# SCH_power_2025-01-19.net
KiCad netlist of a schematic drawn in EasyEDA
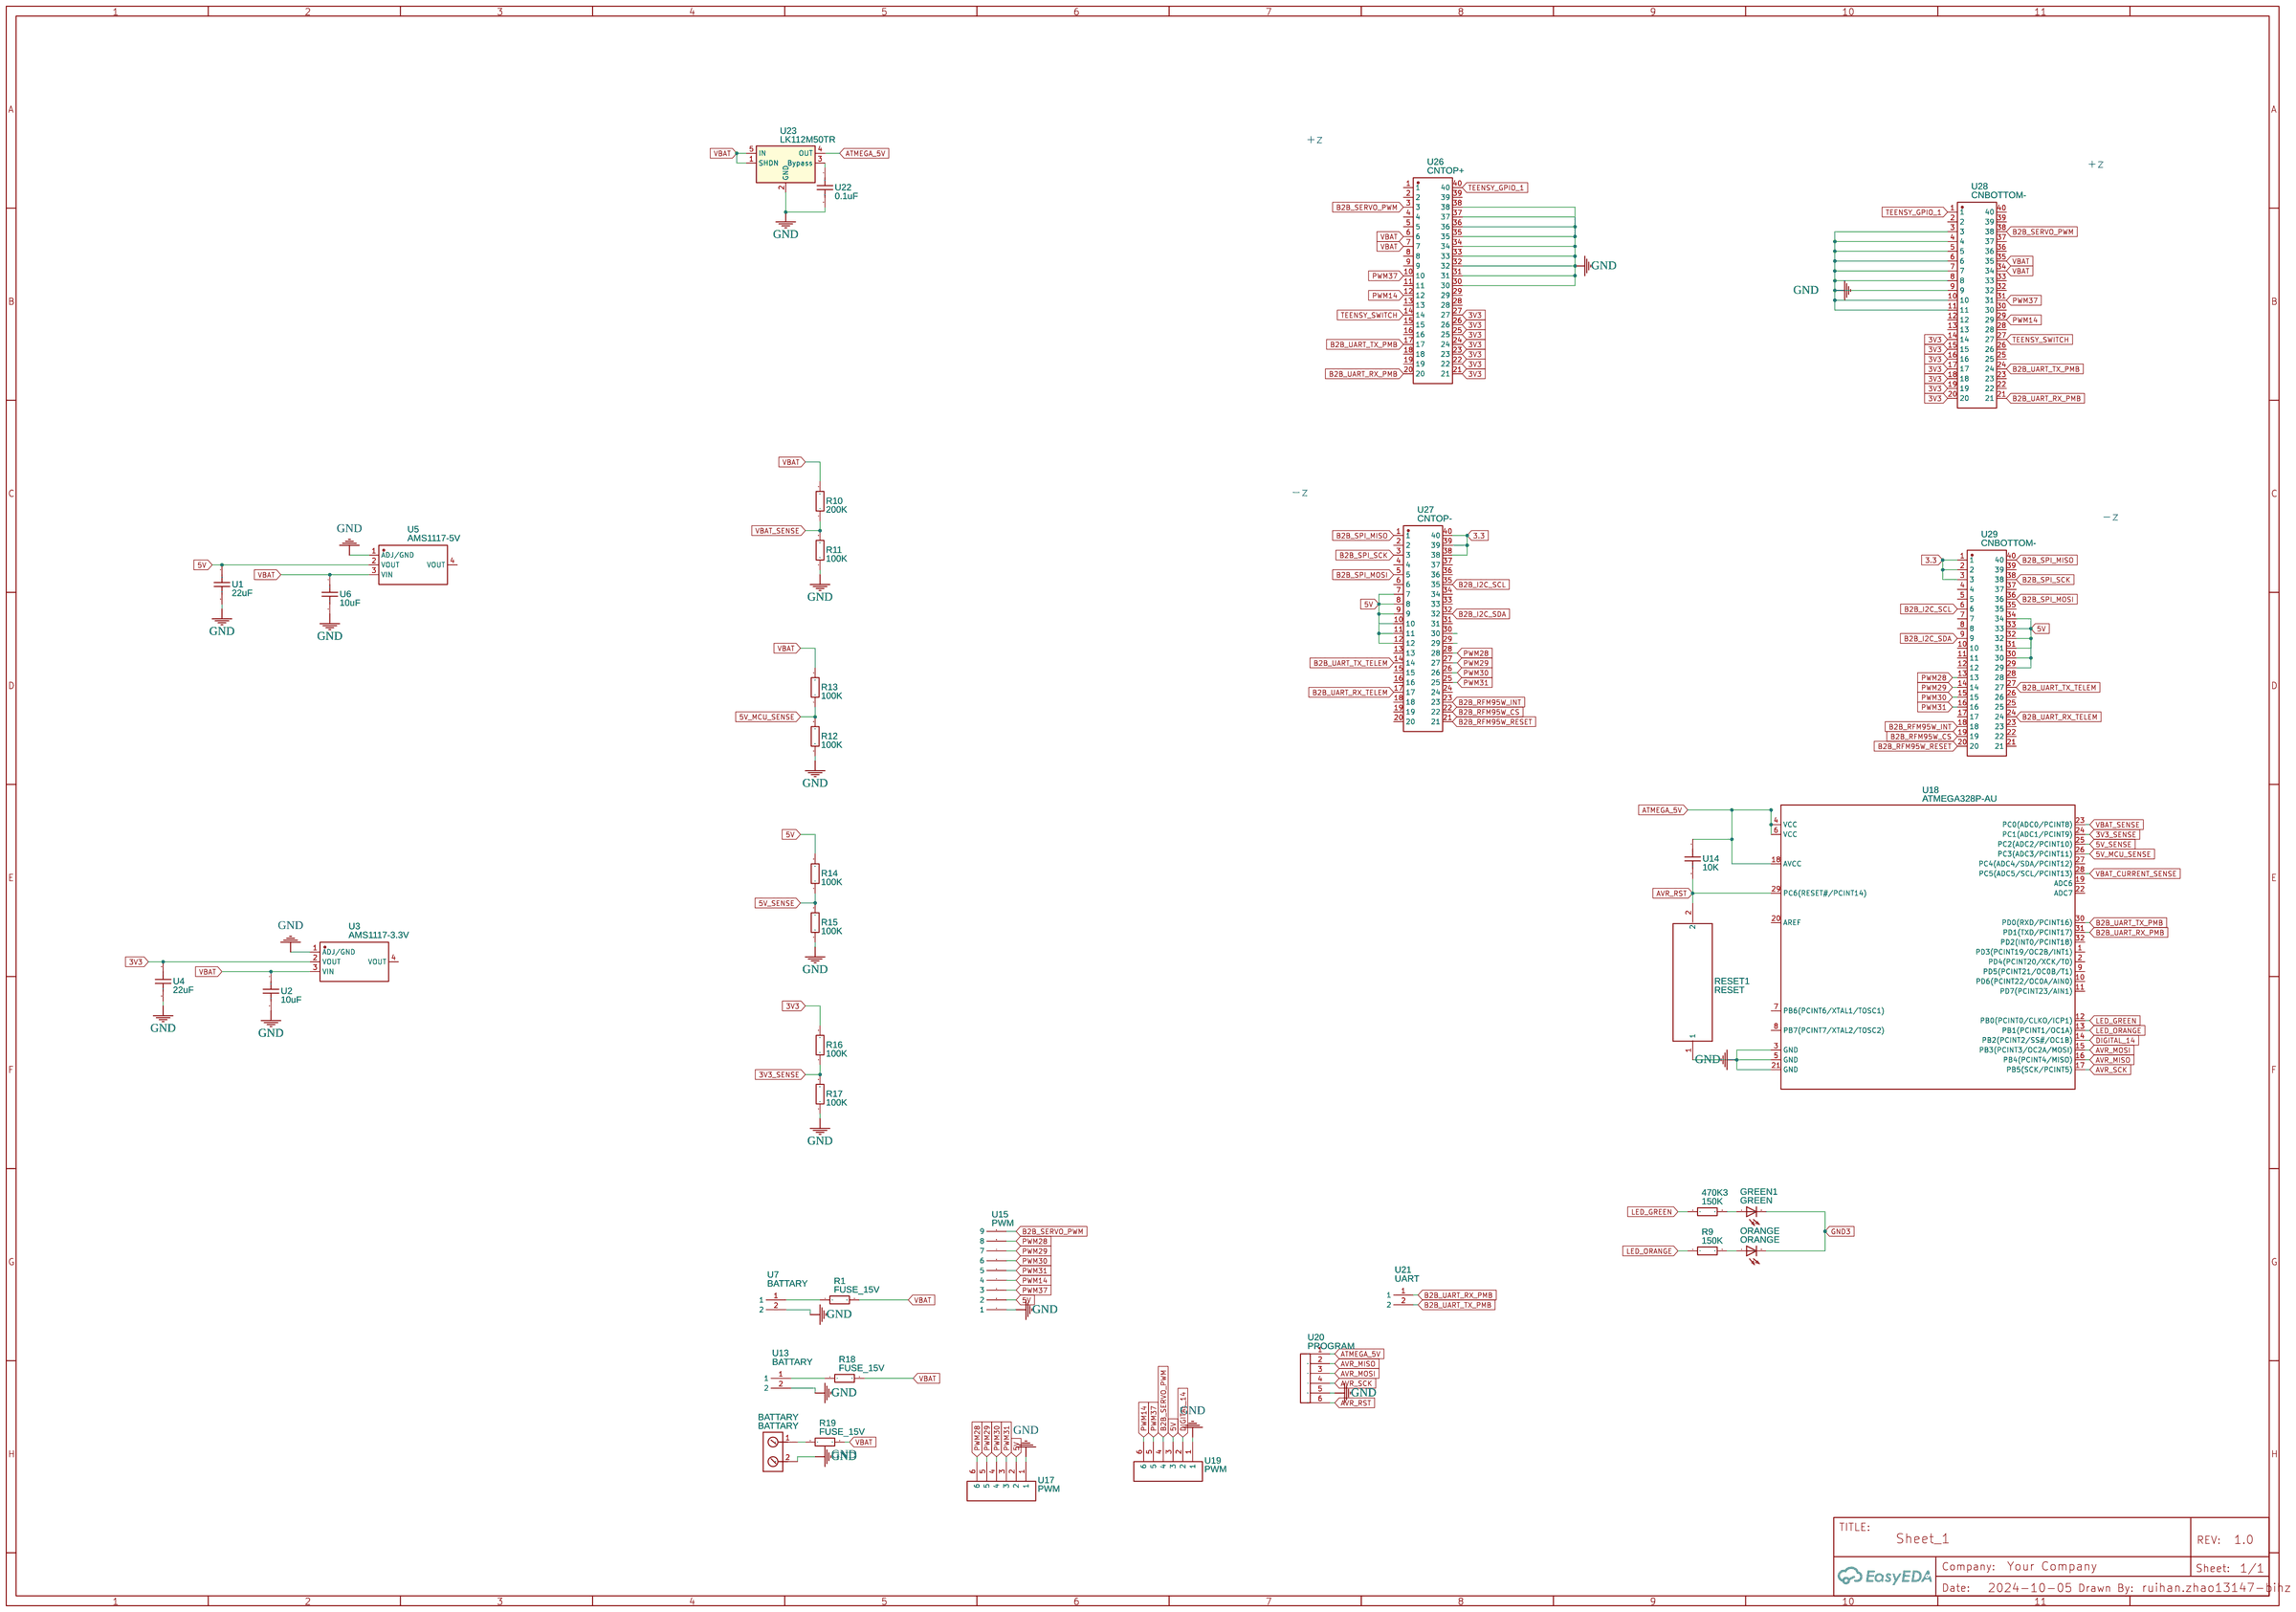
[diagram p0: schematic sheet]

(export (version "E")
  (design (tool "Eeschema 10.0.6"))
  (components
    (comp (ref "470K3") (value "150K") (libsource (lib "") (part "0805 Resistor")))
    (comp (ref "BATTARY") (value "BATTARY") (libsource (lib "") (part "STB-5MM-2PIN")))
    (comp (ref "GREEN1") (value "GREEN") (libsource (lib "") (part "LEDCHIP-LED0805_1")))
    (comp (ref "ORANGE") (value "ORANGE") (libsource (lib "") (part "LEDCHIP-LED0805")))
    (comp (ref "R1")
      (value "FUSE_15V")
      (fields (field (name "Manufacturer Part") "0805"))
      (libsource (lib "") (part "0805_1"))
    )
    (comp (ref "R9") (value "150K") (libsource (lib "") (part "0805 Resistor_1")))
    (comp (ref "R10")
      (value "200K")
      (fields (field (name "Manufacturer Part") "0805"))
      (libsource (lib "") (part "0805"))
    )
    (comp (ref "R11")
      (value "100K")
      (fields (field (name "Manufacturer Part") "0805"))
      (libsource (lib "") (part "0805"))
    )
    (comp (ref "R12")
      (value "100K")
      (fields (field (name "Manufacturer Part") "0805"))
      (libsource (lib "") (part "0805"))
    )
    (comp (ref "R13")
      (value "100K")
      (fields (field (name "Manufacturer Part") "0805"))
      (libsource (lib "") (part "0805"))
    )
    (comp (ref "R14")
      (value "100K")
      (fields (field (name "Manufacturer Part") "0805"))
      (libsource (lib "") (part "0805"))
    )
    (comp (ref "R15")
      (value "100K")
      (fields (field (name "Manufacturer Part") "0805"))
      (libsource (lib "") (part "0805"))
    )
    (comp (ref "R16")
      (value "100K")
      (fields (field (name "Manufacturer Part") "0805"))
      (libsource (lib "") (part "0805"))
    )
    (comp (ref "R17")
      (value "100K")
      (fields (field (name "Manufacturer Part") "0805"))
      (libsource (lib "") (part "0805"))
    )
    (comp (ref "R18")
      (value "FUSE_15V")
      (fields (field (name "Manufacturer Part") "0805"))
      (libsource (lib "") (part "0805_1"))
    )
    (comp (ref "R19")
      (value "FUSE_15V")
      (fields (field (name "Manufacturer Part") "0805"))
      (libsource (lib "") (part "0805_1"))
    )
    (comp (ref "RESET1") (value "RESET") (libsource (lib "") (part "FSMSM")))
    (comp (ref "U1")
      (value "22uF")
      (fields (field (name "Manufacturer Part") "CAP-C0805"))
      (libsource (lib "") (part "CAP-C0805"))
    )
    (comp (ref "U2")
      (value "10uF")
      (fields (field (name "Manufacturer Part") "CAP-C0805"))
      (libsource (lib "") (part "CAP-C0805"))
    )
    (comp (ref "U3")
      (value "AMS1117-3.3V")
      (fields (field (name "Manufacturer") "WPMtek(维攀)"))
      (libsource (lib "") (part "AMS1117-3.3V"))
    )
    (comp (ref "U4")
      (value "22uF")
      (fields (field (name "Manufacturer Part") "CAP-C0805"))
      (libsource (lib "") (part "CAP-C0805"))
    )
    (comp (ref "U5")
      (value "AMS1117-5V")
      (fields (field (name "Manufacturer Part") "AMS1117-3.3V") (field (name "Manufacturer") "WPMtek(维攀)"))
      (libsource (lib "") (part "AMS1117-3.3V"))
    )
    (comp (ref "U6")
      (value "10uF")
      (fields (field (name "Manufacturer Part") "CAP-C0805"))
      (libsource (lib "") (part "CAP-C0805"))
    )
    (comp (ref "U7") (value "BATTARY") (libsource (lib "") (part "2 pin header")))
    (comp (ref "U13") (value "BATTARY") (libsource (lib "") (part "2 pin header")))
    (comp (ref "U14")
      (value "10K")
      (fields (field (name "Manufacturer Part") "CAP-C0805"))
      (libsource (lib "") (part "CAP-C0805"))
    )
    (comp (ref "U15")
      (value "PWM")
      (fields (field (name "Manufacturer Part") "6 Pin Header"))
      (libsource (lib "") (part "9 Pin Header"))
    )
    (comp (ref "U17") (value "PWM") (libsource (lib "") (part "6PIN_5MM")))
    (comp (ref "U18") (value "ATMEGA328P-AU") (libsource (lib "") (part "ATMEGA328P-AU")))
    (comp (ref "U19") (value "PWM") (libsource (lib "") (part "6PIN_5MM")))
    (comp (ref "U20") (value "PROGRAM") (libsource (lib "") (part "6 pin header")))
    (comp (ref "U21") (value "UART") (libsource (lib "") (part "2 pin header")))
    (comp (ref "U22")
      (value "0.1uF")
      (fields (field (name "Manufacturer Part") "CAP-C0805"))
      (libsource (lib "") (part "CAP-C0805"))
    )
    (comp (ref "U23") (value "LK112M50TR") (libsource (lib "") (part "LK112M50TR")))
    (comp (ref "U26")
      (value "CNTOP+")
      (fields (field (name "Manufacturer Part") "SGDBM-08-40P"))
      (libsource (lib "") (part "SGDBM-08-40P"))
    )
    (comp (ref "U27")
      (value "CNTOP-")
      (fields (field (name "Manufacturer Part") "SGDBM-08-40P"))
      (libsource (lib "") (part "SGDBM-08-40P"))
    )
    (comp (ref "U28")
      (value "CNBOTTOM-")
      (fields (field (name "Manufacturer Part") "SGDBM-08-40P"))
      (libsource (lib "") (part "SGDBM-08-40P"))
    )
    (comp (ref "U29")
      (value "CNBOTTOM-")
      (fields (field (name "Manufacturer Part") "SGDBM-08-40P"))
      (libsource (lib "") (part "SGDBM-08-40P"))
    )
  )
  (nets
    (net (code "1") (name "3.3") (class "Default")
      (node (ref "U27") (pin "38") (pinfunction "38_38") (pintype "unspecified"))
      (node (ref "U27") (pin "39") (pinfunction "39_39") (pintype "unspecified"))
      (node (ref "U27") (pin "40") (pinfunction "40_40") (pintype "unspecified"))
      (node (ref "U29") (pin "1") (pinfunction "1_1") (pintype "unspecified"))
      (node (ref "U29") (pin "2") (pinfunction "2_2") (pintype "unspecified"))
      (node (ref "U29") (pin "3") (pinfunction "3_3") (pintype "unspecified"))
    )
    (net (code "2") (name "3V3") (class "Default")
      (node (ref "R16") (pin "2") (pinfunction "2_2") (pintype "unspecified"))
      (node (ref "U26") (pin "21") (pinfunction "21_21") (pintype "unspecified"))
      (node (ref "U26") (pin "22") (pinfunction "22_22") (pintype "unspecified"))
      (node (ref "U26") (pin "23") (pinfunction "23_23") (pintype "unspecified"))
      (node (ref "U26") (pin "24") (pinfunction "24_24") (pintype "unspecified"))
      (node (ref "U26") (pin "25") (pinfunction "25_25") (pintype "unspecified"))
      (node (ref "U26") (pin "26") (pinfunction "26_26") (pintype "unspecified"))
      (node (ref "U26") (pin "27") (pinfunction "27_27") (pintype "unspecified"))
      (node (ref "U28") (pin "14") (pinfunction "14_14") (pintype "unspecified"))
      (node (ref "U28") (pin "15") (pinfunction "15_15") (pintype "unspecified"))
      (node (ref "U28") (pin "16") (pinfunction "16_16") (pintype "unspecified"))
      (node (ref "U28") (pin "17") (pinfunction "17_17") (pintype "unspecified"))
      (node (ref "U28") (pin "18") (pinfunction "18_18") (pintype "unspecified"))
      (node (ref "U28") (pin "19") (pinfunction "19_19") (pintype "unspecified"))
      (node (ref "U28") (pin "20") (pinfunction "20_20") (pintype "unspecified"))
      (node (ref "U3") (pin "2") (pinfunction "VOUT_2") (pintype "unspecified"))
      (node (ref "U4") (pin "1") (pinfunction "1_1") (pintype "unspecified"))
    )
    (net (code "3") (name "3V3_SENSE") (class "Default")
      (node (ref "R16") (pin "1") (pinfunction "1_1") (pintype "unspecified"))
      (node (ref "R17") (pin "2") (pinfunction "2_2") (pintype "unspecified"))
      (node (ref "U18") (pin "24") (pinfunction "PC1(ADC1/PCINT9)_24") (pintype "unspecified"))
    )
    (net (code "4") (name "5V") (class "Default")
      (node (ref "R14") (pin "2") (pinfunction "2_2") (pintype "unspecified"))
      (node (ref "U1") (pin "1") (pinfunction "1_1") (pintype "unspecified"))
      (node (ref "U15") (pin "2") (pinfunction "2_2") (pintype "unspecified"))
      (node (ref "U17") (pin "2") (pinfunction "2_2") (pintype "unspecified"))
      (node (ref "U19") (pin "3") (pinfunction "3_3") (pintype "unspecified"))
      (node (ref "U27") (pin "10") (pinfunction "10_10") (pintype "unspecified"))
      (node (ref "U27") (pin "11") (pinfunction "11_11") (pintype "unspecified"))
      (node (ref "U27") (pin "12") (pinfunction "12_12") (pintype "unspecified"))
      (node (ref "U27") (pin "7") (pinfunction "7_7") (pintype "unspecified"))
      (node (ref "U27") (pin "8") (pinfunction "8_8") (pintype "unspecified"))
      (node (ref "U27") (pin "9") (pinfunction "9_9") (pintype "unspecified"))
      (node (ref "U29") (pin "29") (pinfunction "29_29") (pintype "unspecified"))
      (node (ref "U29") (pin "30") (pinfunction "30_30") (pintype "unspecified"))
      (node (ref "U29") (pin "31") (pinfunction "31_31") (pintype "unspecified"))
      (node (ref "U29") (pin "32") (pinfunction "32_32") (pintype "unspecified"))
      (node (ref "U29") (pin "33") (pinfunction "33_33") (pintype "unspecified"))
      (node (ref "U29") (pin "34") (pinfunction "34_34") (pintype "unspecified"))
      (node (ref "U5") (pin "2") (pinfunction "VOUT_2") (pintype "unspecified"))
    )
    (net (code "5") (name "5V_MCU_SENSE") (class "Default")
      (node (ref "R12") (pin "2") (pinfunction "2_2") (pintype "unspecified"))
      (node (ref "R13") (pin "1") (pinfunction "1_1") (pintype "unspecified"))
      (node (ref "U18") (pin "26") (pinfunction "PC3(ADC3/PCINT11)_26") (pintype "unspecified"))
    )
    (net (code "6") (name "5V_SENSE") (class "Default")
      (node (ref "R14") (pin "1") (pinfunction "1_1") (pintype "unspecified"))
      (node (ref "R15") (pin "2") (pinfunction "2_2") (pintype "unspecified"))
      (node (ref "U18") (pin "25") (pinfunction "PC2(ADC2/PCINT10)_25") (pintype "unspecified"))
    )
    (net (code "7") (name "ATMEGA_5V") (class "Default")
      (node (ref "U14") (pin "1") (pinfunction "1_1") (pintype "unspecified"))
      (node (ref "U18") (pin "18") (pinfunction "AVCC_18") (pintype "unspecified"))
      (node (ref "U18") (pin "4") (pinfunction "VCC_4") (pintype "unspecified"))
      (node (ref "U18") (pin "6") (pinfunction "VCC_6") (pintype "unspecified"))
      (node (ref "U20") (pin "1") (pinfunction "1_1") (pintype "unspecified"))
      (node (ref "U23") (pin "4") (pinfunction "OUT_4") (pintype "bidirectional"))
    )
    (net (code "8") (name "AVR_MISO") (class "Default")
      (node (ref "U18") (pin "16") (pinfunction "PB4(PCINT4/MISO)_16") (pintype "unspecified"))
      (node (ref "U20") (pin "2") (pinfunction "2_2") (pintype "unspecified"))
    )
    (net (code "9") (name "AVR_MOSI") (class "Default")
      (node (ref "U18") (pin "15") (pinfunction "PB3(PCINT3/OC2A/MOSI)_15") (pintype "unspecified"))
      (node (ref "U20") (pin "3") (pinfunction "3_3") (pintype "unspecified"))
    )
    (net (code "10") (name "AVR_RST") (class "Default")
      (node (ref "RESET1") (pin "2") (pinfunction "2_2") (pintype "bidirectional"))
      (node (ref "U14") (pin "2") (pinfunction "2_2") (pintype "unspecified"))
      (node (ref "U18") (pin "29") (pinfunction "PC6(RESET#/PCINT14)_29") (pintype "unspecified"))
      (node (ref "U20") (pin "6") (pinfunction "6_6") (pintype "unspecified"))
    )
    (net (code "11") (name "AVR_SCK") (class "Default")
      (node (ref "U18") (pin "17") (pinfunction "PB5(SCK/PCINT5)_17") (pintype "unspecified"))
      (node (ref "U20") (pin "4") (pinfunction "4_4") (pintype "unspecified"))
    )
    (net (code "12") (name "B2B_I2C_SCL") (class "Default")
      (node (ref "U27") (pin "35") (pinfunction "35_35") (pintype "unspecified"))
      (node (ref "U29") (pin "6") (pinfunction "6_6") (pintype "unspecified"))
    )
    (net (code "13") (name "B2B_I2C_SDA") (class "Default")
      (node (ref "U27") (pin "32") (pinfunction "32_32") (pintype "unspecified"))
      (node (ref "U29") (pin "9") (pinfunction "9_9") (pintype "unspecified"))
    )
    (net (code "14") (name "B2B_RFM95W_CS") (class "Default")
      (node (ref "U27") (pin "22") (pinfunction "22_22") (pintype "unspecified"))
      (node (ref "U29") (pin "19") (pinfunction "19_19") (pintype "unspecified"))
    )
    (net (code "15") (name "B2B_RFM95W_INT") (class "Default")
      (node (ref "U27") (pin "23") (pinfunction "23_23") (pintype "unspecified"))
      (node (ref "U29") (pin "18") (pinfunction "18_18") (pintype "unspecified"))
    )
    (net (code "16") (name "B2B_RFM95W_RESET") (class "Default")
      (node (ref "U27") (pin "21") (pinfunction "21_21") (pintype "unspecified"))
      (node (ref "U29") (pin "20") (pinfunction "20_20") (pintype "unspecified"))
    )
    (net (code "17") (name "B2B_SERVO_PWM") (class "Default")
      (node (ref "U15") (pin "9") (pinfunction "9_9") (pintype "unspecified"))
      (node (ref "U19") (pin "4") (pinfunction "4_4") (pintype "unspecified"))
      (node (ref "U26") (pin "3") (pinfunction "3_3") (pintype "unspecified"))
      (node (ref "U28") (pin "38") (pinfunction "38_38") (pintype "unspecified"))
    )
    (net (code "18") (name "B2B_SPI_MISO") (class "Default")
      (node (ref "U27") (pin "1") (pinfunction "1_1") (pintype "unspecified"))
      (node (ref "U29") (pin "40") (pinfunction "40_40") (pintype "unspecified"))
    )
    (net (code "19") (name "B2B_SPI_MOSI") (class "Default")
      (node (ref "U27") (pin "5") (pinfunction "5_5") (pintype "unspecified"))
      (node (ref "U29") (pin "36") (pinfunction "36_36") (pintype "unspecified"))
    )
    (net (code "20") (name "B2B_SPI_SCK") (class "Default")
      (node (ref "U27") (pin "3") (pinfunction "3_3") (pintype "unspecified"))
      (node (ref "U29") (pin "38") (pinfunction "38_38") (pintype "unspecified"))
    )
    (net (code "21") (name "B2B_UART_RX_PMB") (class "Default")
      (node (ref "U18") (pin "31") (pinfunction "PD1(TXD/PCINT17)_31") (pintype "unspecified"))
      (node (ref "U21") (pin "1") (pinfunction "1_1") (pintype "unspecified"))
      (node (ref "U26") (pin "20") (pinfunction "20_20") (pintype "unspecified"))
      (node (ref "U28") (pin "21") (pinfunction "21_21") (pintype "unspecified"))
    )
    (net (code "22") (name "B2B_UART_RX_TELEM") (class "Default")
      (node (ref "U27") (pin "17") (pinfunction "17_17") (pintype "unspecified"))
      (node (ref "U29") (pin "24") (pinfunction "24_24") (pintype "unspecified"))
    )
    (net (code "23") (name "B2B_UART_TX_PMB") (class "Default")
      (node (ref "U18") (pin "30") (pinfunction "PD0(RXD/PCINT16)_30") (pintype "unspecified"))
      (node (ref "U21") (pin "2") (pinfunction "2_2") (pintype "unspecified"))
      (node (ref "U26") (pin "17") (pinfunction "17_17") (pintype "unspecified"))
      (node (ref "U28") (pin "24") (pinfunction "24_24") (pintype "unspecified"))
    )
    (net (code "24") (name "B2B_UART_TX_TELEM") (class "Default")
      (node (ref "U27") (pin "14") (pinfunction "14_14") (pintype "unspecified"))
      (node (ref "U29") (pin "27") (pinfunction "27_27") (pintype "unspecified"))
    )
    (net (code "25") (name "DIGITAL_14") (class "Default")
      (node (ref "U18") (pin "14") (pinfunction "PB2(PCINT2/SS#/OC1B)_14") (pintype "unspecified"))
      (node (ref "U19") (pin "2") (pinfunction "2_2") (pintype "unspecified"))
    )
    (net (code "26") (name "GND") (class "Default")
      (node (ref "BATTARY") (pin "2") (pinfunction "2_2") (pintype "unspecified"))
      (node (ref "R11") (pin "1") (pinfunction "1_1") (pintype "unspecified"))
      (node (ref "R12") (pin "1") (pinfunction "1_1") (pintype "unspecified"))
      (node (ref "R15") (pin "1") (pinfunction "1_1") (pintype "unspecified"))
      (node (ref "R17") (pin "1") (pinfunction "1_1") (pintype "unspecified"))
      (node (ref "RESET1") (pin "1") (pinfunction "1_1") (pintype "bidirectional"))
      (node (ref "U1") (pin "2") (pinfunction "2_2") (pintype "unspecified"))
      (node (ref "U13") (pin "2") (pinfunction "2_2") (pintype "unspecified"))
      (node (ref "U15") (pin "1") (pinfunction "1_1") (pintype "unspecified"))
      (node (ref "U17") (pin "1") (pinfunction "1_1") (pintype "unspecified"))
      (node (ref "U18") (pin "21") (pinfunction "GND_21") (pintype "unspecified"))
      (node (ref "U18") (pin "3") (pinfunction "GND_3") (pintype "unspecified"))
      (node (ref "U18") (pin "5") (pinfunction "GND_5") (pintype "unspecified"))
      (node (ref "U19") (pin "1") (pinfunction "1_1") (pintype "unspecified"))
      (node (ref "U2") (pin "2") (pinfunction "2_2") (pintype "unspecified"))
      (node (ref "U20") (pin "5") (pinfunction "5_5") (pintype "unspecified"))
      (node (ref "U22") (pin "2") (pinfunction "2_2") (pintype "unspecified"))
      (node (ref "U23") (pin "2") (pinfunction "GND_2") (pintype "bidirectional"))
      (node (ref "U26") (pin "30") (pinfunction "30_30") (pintype "unspecified"))
      (node (ref "U26") (pin "31") (pinfunction "31_31") (pintype "unspecified"))
      (node (ref "U26") (pin "32") (pinfunction "32_32") (pintype "unspecified"))
      (node (ref "U26") (pin "33") (pinfunction "33_33") (pintype "unspecified"))
      (node (ref "U26") (pin "34") (pinfunction "34_34") (pintype "unspecified"))
      (node (ref "U26") (pin "35") (pinfunction "35_35") (pintype "unspecified"))
      (node (ref "U26") (pin "36") (pinfunction "36_36") (pintype "unspecified"))
      (node (ref "U26") (pin "37") (pinfunction "37_37") (pintype "unspecified"))
      (node (ref "U26") (pin "38") (pinfunction "38_38") (pintype "unspecified"))
      (node (ref "U28") (pin "10") (pinfunction "10_10") (pintype "unspecified"))
      (node (ref "U28") (pin "11") (pinfunction "11_11") (pintype "unspecified"))
      (node (ref "U28") (pin "3") (pinfunction "3_3") (pintype "unspecified"))
      (node (ref "U28") (pin "4") (pinfunction "4_4") (pintype "unspecified"))
      (node (ref "U28") (pin "5") (pinfunction "5_5") (pintype "unspecified"))
      (node (ref "U28") (pin "6") (pinfunction "6_6") (pintype "unspecified"))
      (node (ref "U28") (pin "7") (pinfunction "7_7") (pintype "unspecified"))
      (node (ref "U28") (pin "8") (pinfunction "8_8") (pintype "unspecified"))
      (node (ref "U28") (pin "9") (pinfunction "9_9") (pintype "unspecified"))
      (node (ref "U3") (pin "1") (pinfunction "ADJ/GND_1") (pintype "unspecified"))
      (node (ref "U4") (pin "2") (pinfunction "2_2") (pintype "unspecified"))
      (node (ref "U5") (pin "1") (pinfunction "ADJ/GND_1") (pintype "unspecified"))
      (node (ref "U6") (pin "2") (pinfunction "2_2") (pintype "unspecified"))
      (node (ref "U7") (pin "2") (pinfunction "2_2") (pintype "unspecified"))
    )
    (net (code "27") (name "GND3") (class "Default")
      (node (ref "GREEN1") (pin "C") (pinfunction "C_C") (pintype "bidirectional"))
      (node (ref "ORANGE") (pin "C") (pinfunction "C_C") (pintype "bidirectional"))
    )
    (net (code "28") (name "LED_GREEN") (class "Default")
      (node (ref "470K3") (pin "1") (pinfunction "1_1") (pintype "unspecified"))
      (node (ref "U18") (pin "12") (pinfunction "PB0(PCINT0/CLKO/ICP1)_12") (pintype "unspecified"))
    )
    (net (code "29") (name "LED_ORANGE") (class "Default")
      (node (ref "R9") (pin "1") (pinfunction "1_1") (pintype "unspecified"))
      (node (ref "U18") (pin "13") (pinfunction "PB1(PCINT1/OC1A)_13") (pintype "unspecified"))
    )
    (net (code "30") (name "Net-(470K3-Pad2)") (class "Default")
      (node (ref "470K3") (pin "2") (pinfunction "2_2") (pintype "unspecified"))
      (node (ref "GREEN1") (pin "A") (pinfunction "A_A") (pintype "bidirectional"))
    )
    (net (code "31") (name "Net-(BATTARY-Pad1)") (class "Default")
      (node (ref "BATTARY") (pin "1") (pinfunction "1_1") (pintype "unspecified"))
      (node (ref "R19") (pin "1") (pinfunction "1_1") (pintype "unspecified"))
    )
    (net (code "32") (name "Net-(ORANGE-PadA)") (class "Default")
      (node (ref "ORANGE") (pin "A") (pinfunction "A_A") (pintype "bidirectional"))
      (node (ref "R9") (pin "2") (pinfunction "2_2") (pintype "unspecified"))
    )
    (net (code "33") (name "Net-(R1-Pad1)") (class "Default")
      (node (ref "R1") (pin "1") (pinfunction "1_1") (pintype "unspecified"))
      (node (ref "U7") (pin "1") (pinfunction "1_1") (pintype "unspecified"))
    )
    (net (code "34") (name "Net-(R18-Pad1)") (class "Default")
      (node (ref "R18") (pin "1") (pinfunction "1_1") (pintype "unspecified"))
      (node (ref "U13") (pin "1") (pinfunction "1_1") (pintype "unspecified"))
    )
    (net (code "35") (name "Net-(U23-Bypass)") (class "Default")
      (node (ref "U22") (pin "1") (pinfunction "1_1") (pintype "unspecified"))
      (node (ref "U23") (pin "3") (pinfunction "Bypass_3") (pintype "unspecified"))
    )
    (net (code "36") (name "PWM14") (class "Default")
      (node (ref "U15") (pin "4") (pinfunction "4_4") (pintype "unspecified"))
      (node (ref "U19") (pin "6") (pinfunction "6_6") (pintype "unspecified"))
      (node (ref "U26") (pin "12") (pinfunction "12_12") (pintype "unspecified"))
      (node (ref "U28") (pin "29") (pinfunction "29_29") (pintype "unspecified"))
    )
    (net (code "37") (name "PWM28") (class "Default")
      (node (ref "U15") (pin "8") (pinfunction "8_8") (pintype "unspecified"))
      (node (ref "U17") (pin "6") (pinfunction "6_6") (pintype "unspecified"))
      (node (ref "U27") (pin "28") (pinfunction "28_28") (pintype "unspecified"))
      (node (ref "U29") (pin "13") (pinfunction "13_13") (pintype "unspecified"))
    )
    (net (code "38") (name "PWM29") (class "Default")
      (node (ref "U15") (pin "7") (pinfunction "7_7") (pintype "unspecified"))
      (node (ref "U17") (pin "5") (pinfunction "5_5") (pintype "unspecified"))
      (node (ref "U27") (pin "27") (pinfunction "27_27") (pintype "unspecified"))
      (node (ref "U29") (pin "14") (pinfunction "14_14") (pintype "unspecified"))
    )
    (net (code "39") (name "PWM30") (class "Default")
      (node (ref "U15") (pin "6") (pinfunction "6_6") (pintype "unspecified"))
      (node (ref "U17") (pin "4") (pinfunction "4_4") (pintype "unspecified"))
      (node (ref "U27") (pin "26") (pinfunction "26_26") (pintype "unspecified"))
      (node (ref "U29") (pin "15") (pinfunction "15_15") (pintype "unspecified"))
    )
    (net (code "40") (name "PWM31") (class "Default")
      (node (ref "U15") (pin "5") (pinfunction "5_5") (pintype "unspecified"))
      (node (ref "U17") (pin "3") (pinfunction "3_3") (pintype "unspecified"))
      (node (ref "U27") (pin "25") (pinfunction "25_25") (pintype "unspecified"))
      (node (ref "U29") (pin "16") (pinfunction "16_16") (pintype "unspecified"))
    )
    (net (code "41") (name "PWM37") (class "Default")
      (node (ref "U15") (pin "3") (pinfunction "3_3") (pintype "unspecified"))
      (node (ref "U19") (pin "5") (pinfunction "5_5") (pintype "unspecified"))
      (node (ref "U26") (pin "10") (pinfunction "10_10") (pintype "unspecified"))
      (node (ref "U28") (pin "31") (pinfunction "31_31") (pintype "unspecified"))
    )
    (net (code "42") (name "TEENSY_GPIO_1") (class "Default")
      (node (ref "U26") (pin "40") (pinfunction "40_40") (pintype "unspecified"))
      (node (ref "U28") (pin "1") (pinfunction "1_1") (pintype "unspecified"))
    )
    (net (code "43") (name "TEENSY_SWITCH") (class "Default")
      (node (ref "U26") (pin "14") (pinfunction "14_14") (pintype "unspecified"))
      (node (ref "U28") (pin "27") (pinfunction "27_27") (pintype "unspecified"))
    )
    (net (code "44") (name "VBAT") (class "Default")
      (node (ref "R1") (pin "2") (pinfunction "2_2") (pintype "unspecified"))
      (node (ref "R10") (pin "2") (pinfunction "2_2") (pintype "unspecified"))
      (node (ref "R13") (pin "2") (pinfunction "2_2") (pintype "unspecified"))
      (node (ref "R18") (pin "2") (pinfunction "2_2") (pintype "unspecified"))
      (node (ref "R19") (pin "2") (pinfunction "2_2") (pintype "unspecified"))
      (node (ref "U2") (pin "1") (pinfunction "1_1") (pintype "unspecified"))
      (node (ref "U23") (pin "1") (pinfunction "SHDN_1") (pintype "input"))
      (node (ref "U23") (pin "5") (pinfunction "IN_5") (pintype "bidirectional"))
      (node (ref "U26") (pin "6") (pinfunction "6_6") (pintype "unspecified"))
      (node (ref "U26") (pin "7") (pinfunction "7_7") (pintype "unspecified"))
      (node (ref "U28") (pin "34") (pinfunction "34_34") (pintype "unspecified"))
      (node (ref "U28") (pin "35") (pinfunction "35_35") (pintype "unspecified"))
      (node (ref "U3") (pin "3") (pinfunction "VIN_3") (pintype "unspecified"))
      (node (ref "U5") (pin "3") (pinfunction "VIN_3") (pintype "unspecified"))
      (node (ref "U6") (pin "1") (pinfunction "1_1") (pintype "unspecified"))
    )
    (net (code "45") (name "VBAT_CURRENT_SENSE") (class "Default")
      (node (ref "U18") (pin "28") (pinfunction "PC5(ADC5/SCL/PCINT13)_28") (pintype "unspecified"))
    )
    (net (code "46") (name "VBAT_SENSE") (class "Default")
      (node (ref "R10") (pin "1") (pinfunction "1_1") (pintype "unspecified"))
      (node (ref "R11") (pin "2") (pinfunction "2_2") (pintype "unspecified"))
      (node (ref "U18") (pin "23") (pinfunction "PC0(ADC0/PCINT8)_23") (pintype "unspecified"))
    )
    (net (code "47") (name "unconnected-(U3-VOUT-Pad4)") (class "Default")
      (node (ref "U3") (pin "4") (pinfunction "VOUT_4") (pintype "unspecified"))
    )
    (net (code "48") (name "unconnected-(U5-VOUT-Pad4)") (class "Default")
      (node (ref "U5") (pin "4") (pinfunction "VOUT_4") (pintype "unspecified"))
    )
    (net (code "49") (name "unconnected-(U18-ADC6-Pad19)") (class "Default")
      (node (ref "U18") (pin "19") (pinfunction "ADC6_19") (pintype "unspecified"))
    )
    (net (code "50") (name "unconnected-(U18-ADC7-Pad22)") (class "Default")
      (node (ref "U18") (pin "22") (pinfunction "ADC7_22") (pintype "unspecified"))
    )
    (net (code "51") (name "unconnected-(U18-AREF-Pad20)") (class "Default")
      (node (ref "U18") (pin "20") (pinfunction "AREF_20") (pintype "unspecified"))
    )
    (net (code "52") (name "unconnected-(U18-PB6(PCINT6{slash}XTAL1{slash}TOSC1)-Pad7)") (class "Default")
      (node (ref "U18") (pin "7") (pinfunction "PB6(PCINT6/XTAL1/TOSC1)_7") (pintype "unspecified"))
    )
    (net (code "53") (name "unconnected-(U18-PB7(PCINT7{slash}XTAL2{slash}TOSC2)-Pad8)") (class "Default")
      (node (ref "U18") (pin "8") (pinfunction "PB7(PCINT7/XTAL2/TOSC2)_8") (pintype "unspecified"))
    )
    (net (code "54") (name "unconnected-(U18-PC4(ADC4{slash}SDA{slash}PCINT12)-Pad27)") (class "Default")
      (node (ref "U18") (pin "27") (pinfunction "PC4(ADC4/SDA/PCINT12)_27") (pintype "unspecified"))
    )
    (net (code "55") (name "unconnected-(U18-PD2(INT0{slash}PCINT18)-Pad32)") (class "Default")
      (node (ref "U18") (pin "32") (pinfunction "PD2(INT0/PCINT18)_32") (pintype "unspecified"))
    )
    (net (code "56") (name "unconnected-(U18-PD3(PCINT19{slash}OC2B{slash}INT1)-Pad1)") (class "Default")
      (node (ref "U18") (pin "1") (pinfunction "PD3(PCINT19/OC2B/INT1)_1") (pintype "unspecified"))
    )
    (net (code "57") (name "unconnected-(U18-PD4(PCINT20{slash}XCK{slash}T0)-Pad2)") (class "Default")
      (node (ref "U18") (pin "2") (pinfunction "PD4(PCINT20/XCK/T0)_2") (pintype "unspecified"))
    )
    (net (code "58") (name "unconnected-(U18-PD5(PCINT21{slash}OC0B{slash}T1)-Pad9)") (class "Default")
      (node (ref "U18") (pin "9") (pinfunction "PD5(PCINT21/OC0B/T1)_9") (pintype "unspecified"))
    )
    (net (code "59") (name "unconnected-(U18-PD6(PCINT22{slash}OC0A{slash}AIN0)-Pad10)") (class "Default")
      (node (ref "U18") (pin "10") (pinfunction "PD6(PCINT22/OC0A/AIN0)_10") (pintype "unspecified"))
    )
    (net (code "60") (name "unconnected-(U18-PD7(PCINT23{slash}AIN1)-Pad11)") (class "Default")
      (node (ref "U18") (pin "11") (pinfunction "PD7(PCINT23/AIN1)_11") (pintype "unspecified"))
    )
    (net (code "61") (name "unconnected-(U26-Pad1)") (class "Default")
      (node (ref "U26") (pin "1") (pinfunction "1_1") (pintype "unspecified"))
    )
    (net (code "62") (name "unconnected-(U26-Pad2)") (class "Default")
      (node (ref "U26") (pin "2") (pinfunction "2_2") (pintype "unspecified"))
    )
    (net (code "63") (name "unconnected-(U26-Pad4)") (class "Default")
      (node (ref "U26") (pin "4") (pinfunction "4_4") (pintype "unspecified"))
    )
    (net (code "64") (name "unconnected-(U26-Pad5)") (class "Default")
      (node (ref "U26") (pin "5") (pinfunction "5_5") (pintype "unspecified"))
    )
    (net (code "65") (name "unconnected-(U26-Pad8)") (class "Default")
      (node (ref "U26") (pin "8") (pinfunction "8_8") (pintype "unspecified"))
    )
    (net (code "66") (name "unconnected-(U26-Pad9)") (class "Default")
      (node (ref "U26") (pin "9") (pinfunction "9_9") (pintype "unspecified"))
    )
    (net (code "67") (name "unconnected-(U26-Pad11)") (class "Default")
      (node (ref "U26") (pin "11") (pinfunction "11_11") (pintype "unspecified"))
    )
    (net (code "68") (name "unconnected-(U26-Pad13)") (class "Default")
      (node (ref "U26") (pin "13") (pinfunction "13_13") (pintype "unspecified"))
    )
    (net (code "69") (name "unconnected-(U26-Pad15)") (class "Default")
      (node (ref "U26") (pin "15") (pinfunction "15_15") (pintype "unspecified"))
    )
    (net (code "70") (name "unconnected-(U26-Pad16)") (class "Default")
      (node (ref "U26") (pin "16") (pinfunction "16_16") (pintype "unspecified"))
    )
    (net (code "71") (name "unconnected-(U26-Pad18)") (class "Default")
      (node (ref "U26") (pin "18") (pinfunction "18_18") (pintype "unspecified"))
    )
    (net (code "72") (name "unconnected-(U26-Pad19)") (class "Default")
      (node (ref "U26") (pin "19") (pinfunction "19_19") (pintype "unspecified"))
    )
    (net (code "73") (name "unconnected-(U26-Pad28)") (class "Default")
      (node (ref "U26") (pin "28") (pinfunction "28_28") (pintype "unspecified"))
    )
    (net (code "74") (name "unconnected-(U26-Pad29)") (class "Default")
      (node (ref "U26") (pin "29") (pinfunction "29_29") (pintype "unspecified"))
    )
    (net (code "75") (name "unconnected-(U26-Pad39)") (class "Default")
      (node (ref "U26") (pin "39") (pinfunction "39_39") (pintype "unspecified"))
    )
    (net (code "76") (name "unconnected-(U27-Pad2)") (class "Default")
      (node (ref "U27") (pin "2") (pinfunction "2_2") (pintype "unspecified"))
    )
    (net (code "77") (name "unconnected-(U27-Pad4)") (class "Default")
      (node (ref "U27") (pin "4") (pinfunction "4_4") (pintype "unspecified"))
    )
    (net (code "78") (name "unconnected-(U27-Pad6)") (class "Default")
      (node (ref "U27") (pin "6") (pinfunction "6_6") (pintype "unspecified"))
    )
    (net (code "79") (name "unconnected-(U27-Pad13)") (class "Default")
      (node (ref "U27") (pin "13") (pinfunction "13_13") (pintype "unspecified"))
    )
    (net (code "80") (name "unconnected-(U27-Pad15)") (class "Default")
      (node (ref "U27") (pin "15") (pinfunction "15_15") (pintype "unspecified"))
    )
    (net (code "81") (name "unconnected-(U27-Pad16)") (class "Default")
      (node (ref "U27") (pin "16") (pinfunction "16_16") (pintype "unspecified"))
    )
    (net (code "82") (name "unconnected-(U27-Pad18)") (class "Default")
      (node (ref "U27") (pin "18") (pinfunction "18_18") (pintype "unspecified"))
    )
    (net (code "83") (name "unconnected-(U27-Pad19)") (class "Default")
      (node (ref "U27") (pin "19") (pinfunction "19_19") (pintype "unspecified"))
    )
    (net (code "84") (name "unconnected-(U27-Pad20)") (class "Default")
      (node (ref "U27") (pin "20") (pinfunction "20_20") (pintype "unspecified"))
    )
    (net (code "85") (name "unconnected-(U27-Pad24)") (class "Default")
      (node (ref "U27") (pin "24") (pinfunction "24_24") (pintype "unspecified"))
    )
    (net (code "86") (name "unconnected-(U27-Pad29)") (class "Default")
      (node (ref "U27") (pin "29") (pinfunction "29_29") (pintype "unspecified"))
    )
    (net (code "87") (name "unconnected-(U27-Pad30)") (class "Default")
      (node (ref "U27") (pin "30") (pinfunction "30_30") (pintype "unspecified"))
    )
    (net (code "88") (name "unconnected-(U27-Pad31)") (class "Default")
      (node (ref "U27") (pin "31") (pinfunction "31_31") (pintype "unspecified"))
    )
    (net (code "89") (name "unconnected-(U27-Pad33)") (class "Default")
      (node (ref "U27") (pin "33") (pinfunction "33_33") (pintype "unspecified"))
    )
    (net (code "90") (name "unconnected-(U27-Pad34)") (class "Default")
      (node (ref "U27") (pin "34") (pinfunction "34_34") (pintype "unspecified"))
    )
    (net (code "91") (name "unconnected-(U27-Pad36)") (class "Default")
      (node (ref "U27") (pin "36") (pinfunction "36_36") (pintype "unspecified"))
    )
    (net (code "92") (name "unconnected-(U27-Pad37)") (class "Default")
      (node (ref "U27") (pin "37") (pinfunction "37_37") (pintype "unspecified"))
    )
    (net (code "93") (name "unconnected-(U28-Pad2)") (class "Default")
      (node (ref "U28") (pin "2") (pinfunction "2_2") (pintype "unspecified"))
    )
    (net (code "94") (name "unconnected-(U28-Pad12)") (class "Default")
      (node (ref "U28") (pin "12") (pinfunction "12_12") (pintype "unspecified"))
    )
    (net (code "95") (name "unconnected-(U28-Pad13)") (class "Default")
      (node (ref "U28") (pin "13") (pinfunction "13_13") (pintype "unspecified"))
    )
    (net (code "96") (name "unconnected-(U28-Pad22)") (class "Default")
      (node (ref "U28") (pin "22") (pinfunction "22_22") (pintype "unspecified"))
    )
    (net (code "97") (name "unconnected-(U28-Pad23)") (class "Default")
      (node (ref "U28") (pin "23") (pinfunction "23_23") (pintype "unspecified"))
    )
    (net (code "98") (name "unconnected-(U28-Pad25)") (class "Default")
      (node (ref "U28") (pin "25") (pinfunction "25_25") (pintype "unspecified"))
    )
    (net (code "99") (name "unconnected-(U28-Pad26)") (class "Default")
      (node (ref "U28") (pin "26") (pinfunction "26_26") (pintype "unspecified"))
    )
    (net (code "100") (name "unconnected-(U28-Pad28)") (class "Default")
      (node (ref "U28") (pin "28") (pinfunction "28_28") (pintype "unspecified"))
    )
    (net (code "101") (name "unconnected-(U28-Pad30)") (class "Default")
      (node (ref "U28") (pin "30") (pinfunction "30_30") (pintype "unspecified"))
    )
    (net (code "102") (name "unconnected-(U28-Pad32)") (class "Default")
      (node (ref "U28") (pin "32") (pinfunction "32_32") (pintype "unspecified"))
    )
    (net (code "103") (name "unconnected-(U28-Pad33)") (class "Default")
      (node (ref "U28") (pin "33") (pinfunction "33_33") (pintype "unspecified"))
    )
    (net (code "104") (name "unconnected-(U28-Pad36)") (class "Default")
      (node (ref "U28") (pin "36") (pinfunction "36_36") (pintype "unspecified"))
    )
    (net (code "105") (name "unconnected-(U28-Pad37)") (class "Default")
      (node (ref "U28") (pin "37") (pinfunction "37_37") (pintype "unspecified"))
    )
    (net (code "106") (name "unconnected-(U28-Pad39)") (class "Default")
      (node (ref "U28") (pin "39") (pinfunction "39_39") (pintype "unspecified"))
    )
    (net (code "107") (name "unconnected-(U28-Pad40)") (class "Default")
      (node (ref "U28") (pin "40") (pinfunction "40_40") (pintype "unspecified"))
    )
    (net (code "108") (name "unconnected-(U29-Pad4)") (class "Default")
      (node (ref "U29") (pin "4") (pinfunction "4_4") (pintype "unspecified"))
    )
    (net (code "109") (name "unconnected-(U29-Pad5)") (class "Default")
      (node (ref "U29") (pin "5") (pinfunction "5_5") (pintype "unspecified"))
    )
    (net (code "110") (name "unconnected-(U29-Pad7)") (class "Default")
      (node (ref "U29") (pin "7") (pinfunction "7_7") (pintype "unspecified"))
    )
    (net (code "111") (name "unconnected-(U29-Pad8)") (class "Default")
      (node (ref "U29") (pin "8") (pinfunction "8_8") (pintype "unspecified"))
    )
    (net (code "112") (name "unconnected-(U29-Pad10)") (class "Default")
      (node (ref "U29") (pin "10") (pinfunction "10_10") (pintype "unspecified"))
    )
    (net (code "113") (name "unconnected-(U29-Pad11)") (class "Default")
      (node (ref "U29") (pin "11") (pinfunction "11_11") (pintype "unspecified"))
    )
    (net (code "114") (name "unconnected-(U29-Pad12)") (class "Default")
      (node (ref "U29") (pin "12") (pinfunction "12_12") (pintype "unspecified"))
    )
    (net (code "115") (name "unconnected-(U29-Pad17)") (class "Default")
      (node (ref "U29") (pin "17") (pinfunction "17_17") (pintype "unspecified"))
    )
    (net (code "116") (name "unconnected-(U29-Pad21)") (class "Default")
      (node (ref "U29") (pin "21") (pinfunction "21_21") (pintype "unspecified"))
    )
    (net (code "117") (name "unconnected-(U29-Pad22)") (class "Default")
      (node (ref "U29") (pin "22") (pinfunction "22_22") (pintype "unspecified"))
    )
    (net (code "118") (name "unconnected-(U29-Pad23)") (class "Default")
      (node (ref "U29") (pin "23") (pinfunction "23_23") (pintype "unspecified"))
    )
    (net (code "119") (name "unconnected-(U29-Pad25)") (class "Default")
      (node (ref "U29") (pin "25") (pinfunction "25_25") (pintype "unspecified"))
    )
    (net (code "120") (name "unconnected-(U29-Pad26)") (class "Default")
      (node (ref "U29") (pin "26") (pinfunction "26_26") (pintype "unspecified"))
    )
    (net (code "121") (name "unconnected-(U29-Pad28)") (class "Default")
      (node (ref "U29") (pin "28") (pinfunction "28_28") (pintype "unspecified"))
    )
    (net (code "122") (name "unconnected-(U29-Pad35)") (class "Default")
      (node (ref "U29") (pin "35") (pinfunction "35_35") (pintype "unspecified"))
    )
    (net (code "123") (name "unconnected-(U29-Pad37)") (class "Default")
      (node (ref "U29") (pin "37") (pinfunction "37_37") (pintype "unspecified"))
    )
    (net (code "124") (name "unconnected-(U29-Pad39)") (class "Default")
      (node (ref "U29") (pin "39") (pinfunction "39_39") (pintype "unspecified"))
    )
  )
)
